# headers.net
KiCad netlist of a schematic drawn in Altium Designer
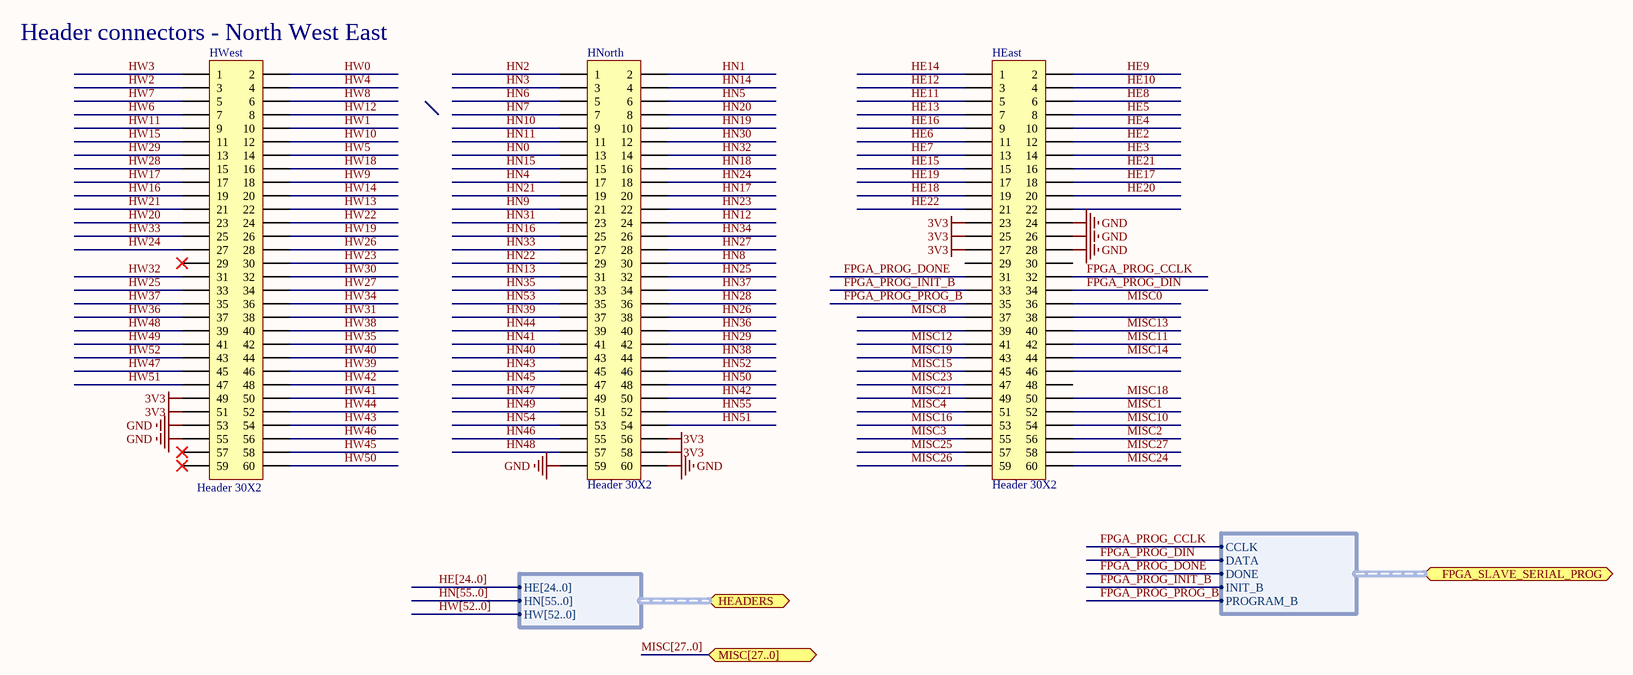
[diagram p0: headers.SchDoc]

(export (version "E")
  (design (tool "Eeschema 10.0.6"))
  (components
    (comp (ref "HEast")
      (value "Header 30X2")
      (footprint "HDR2X30")
      (description "Header, 30-Pin, Dual row")
      (fields (field (name "PUBLISHER") "Altium Limited"))
      (libsource (lib "Miscellaneous Connectors") (part "Header 30X2"))
    )
    (comp (ref "HNorth")
      (value "Header 30X2")
      (footprint "HDR2X30")
      (description "Header, 30-Pin, Dual row")
      (fields (field (name "PUBLISHER") "Altium Limited"))
      (libsource (lib "Miscellaneous Connectors") (part "Header 30X2"))
    )
    (comp (ref "HWest")
      (value "Header 30X2")
      (footprint "HDR2X30")
      (description "Header, 30-Pin, Dual row")
      (fields (field (name "PUBLISHER") "Altium Limited"))
      (libsource (lib "Miscellaneous Connectors") (part "Header 30X2"))
    )
  )
  (nets
    (net (code "10") (name "/FPGA_PROG_CCLK") (class "Default")
      (node (ref "HEast") (pin "32") (pinfunction "32_32") (pintype "passive"))
    )
    (net (code "11") (name "/FPGA_PROG_DIN") (class "Default")
      (node (ref "HEast") (pin "34") (pinfunction "34_34") (pintype "passive"))
    )
    (net (code "12") (name "/FPGA_PROG_DONE") (class "Default")
      (node (ref "HEast") (pin "31") (pinfunction "31_31") (pintype "passive"))
    )
    (net (code "13") (name "/FPGA_PROG_INIT_B") (class "Default")
      (node (ref "HEast") (pin "33") (pinfunction "33_33") (pintype "passive"))
    )
    (net (code "14") (name "/FPGA_PROG_PROG_B") (class "Default")
      (node (ref "HEast") (pin "35") (pinfunction "35_35") (pintype "passive"))
    )
    (net (code "15") (name "/HE2") (class "Default")
      (node (ref "HEast") (pin "12") (pinfunction "12_12") (pintype "passive"))
    )
    (net (code "16") (name "/HE3") (class "Default")
      (node (ref "HEast") (pin "14") (pinfunction "14_14") (pintype "passive"))
    )
    (net (code "17") (name "/HE4") (class "Default")
      (node (ref "HEast") (pin "10") (pinfunction "10_10") (pintype "passive"))
    )
    (net (code "18") (name "/HE5") (class "Default")
      (node (ref "HEast") (pin "8") (pinfunction "8_8") (pintype "passive"))
    )
    (net (code "19") (name "/HE6") (class "Default")
      (node (ref "HEast") (pin "11") (pinfunction "11_11") (pintype "passive"))
    )
    (net (code "20") (name "/HE7") (class "Default")
      (node (ref "HEast") (pin "13") (pinfunction "13_13") (pintype "passive"))
    )
    (net (code "21") (name "/HE8") (class "Default")
      (node (ref "HEast") (pin "6") (pinfunction "6_6") (pintype "passive"))
    )
    (net (code "22") (name "/HE9") (class "Default")
      (node (ref "HEast") (pin "2") (pinfunction "2_2") (pintype "passive"))
    )
    (net (code "23") (name "/HE10") (class "Default")
      (node (ref "HEast") (pin "4") (pinfunction "4_4") (pintype "passive"))
    )
    (net (code "24") (name "/HE11") (class "Default")
      (node (ref "HEast") (pin "5") (pinfunction "5_5") (pintype "passive"))
    )
    (net (code "25") (name "/HE12") (class "Default")
      (node (ref "HEast") (pin "3") (pinfunction "3_3") (pintype "passive"))
    )
    (net (code "26") (name "/HE13") (class "Default")
      (node (ref "HEast") (pin "7") (pinfunction "7_7") (pintype "passive"))
    )
    (net (code "27") (name "/HE14") (class "Default")
      (node (ref "HEast") (pin "1") (pinfunction "1_1") (pintype "passive"))
    )
    (net (code "28") (name "/HE15") (class "Default")
      (node (ref "HEast") (pin "15") (pinfunction "15_15") (pintype "passive"))
    )
    (net (code "29") (name "/HE16") (class "Default")
      (node (ref "HEast") (pin "9") (pinfunction "9_9") (pintype "passive"))
    )
    (net (code "30") (name "/HE17") (class "Default")
      (node (ref "HEast") (pin "18") (pinfunction "18_18") (pintype "passive"))
    )
    (net (code "31") (name "/HE18") (class "Default")
      (node (ref "HEast") (pin "19") (pinfunction "19_19") (pintype "passive"))
    )
    (net (code "32") (name "/HE19") (class "Default")
      (node (ref "HEast") (pin "17") (pinfunction "17_17") (pintype "passive"))
    )
    (net (code "33") (name "/HE20") (class "Default")
      (node (ref "HEast") (pin "20") (pinfunction "20_20") (pintype "passive"))
    )
    (net (code "34") (name "/HE21") (class "Default")
      (node (ref "HEast") (pin "16") (pinfunction "16_16") (pintype "passive"))
    )
    (net (code "35") (name "/HE22") (class "Default")
      (node (ref "HEast") (pin "21") (pinfunction "21_21") (pintype "passive"))
    )
    (net (code "37") (name "/HN0") (class "Default")
      (node (ref "HNorth") (pin "13") (pinfunction "13_13") (pintype "passive"))
    )
    (net (code "38") (name "/HN1") (class "Default")
      (node (ref "HNorth") (pin "2") (pinfunction "2_2") (pintype "passive"))
    )
    (net (code "39") (name "/HN2") (class "Default")
      (node (ref "HNorth") (pin "1") (pinfunction "1_1") (pintype "passive"))
    )
    (net (code "40") (name "/HN3") (class "Default")
      (node (ref "HNorth") (pin "3") (pinfunction "3_3") (pintype "passive"))
    )
    (net (code "41") (name "/HN4") (class "Default")
      (node (ref "HNorth") (pin "17") (pinfunction "17_17") (pintype "passive"))
    )
    (net (code "42") (name "/HN5") (class "Default")
      (node (ref "HNorth") (pin "6") (pinfunction "6_6") (pintype "passive"))
    )
    (net (code "43") (name "/HN6") (class "Default")
      (node (ref "HNorth") (pin "5") (pinfunction "5_5") (pintype "passive"))
    )
    (net (code "44") (name "/HN7") (class "Default")
      (node (ref "HNorth") (pin "7") (pinfunction "7_7") (pintype "passive"))
    )
    (net (code "45") (name "/HN8") (class "Default")
      (node (ref "HNorth") (pin "30") (pinfunction "30_30") (pintype "passive"))
    )
    (net (code "46") (name "/HN9") (class "Default")
      (node (ref "HNorth") (pin "21") (pinfunction "21_21") (pintype "passive"))
    )
    (net (code "47") (name "/HN10") (class "Default")
      (node (ref "HNorth") (pin "9") (pinfunction "9_9") (pintype "passive"))
    )
    (net (code "48") (name "/HN11") (class "Default")
      (node (ref "HNorth") (pin "11") (pinfunction "11_11") (pintype "passive"))
    )
    (net (code "49") (name "/HN12") (class "Default")
      (node (ref "HNorth") (pin "24") (pinfunction "24_24") (pintype "passive"))
    )
    (net (code "50") (name "/HN13") (class "Default")
      (node (ref "HNorth") (pin "31") (pinfunction "31_31") (pintype "passive"))
    )
    (net (code "51") (name "/HN14") (class "Default")
      (node (ref "HNorth") (pin "4") (pinfunction "4_4") (pintype "passive"))
    )
    (net (code "52") (name "/HN15") (class "Default")
      (node (ref "HNorth") (pin "15") (pinfunction "15_15") (pintype "passive"))
    )
    (net (code "53") (name "/HN16") (class "Default")
      (node (ref "HNorth") (pin "25") (pinfunction "25_25") (pintype "passive"))
    )
    (net (code "54") (name "/HN17") (class "Default")
      (node (ref "HNorth") (pin "20") (pinfunction "20_20") (pintype "passive"))
    )
    (net (code "55") (name "/HN18") (class "Default")
      (node (ref "HNorth") (pin "16") (pinfunction "16_16") (pintype "passive"))
    )
    (net (code "56") (name "/HN19") (class "Default")
      (node (ref "HNorth") (pin "10") (pinfunction "10_10") (pintype "passive"))
    )
    (net (code "57") (name "/HN20") (class "Default")
      (node (ref "HNorth") (pin "8") (pinfunction "8_8") (pintype "passive"))
    )
    (net (code "58") (name "/HN21") (class "Default")
      (node (ref "HNorth") (pin "19") (pinfunction "19_19") (pintype "passive"))
    )
    (net (code "59") (name "/HN22") (class "Default")
      (node (ref "HNorth") (pin "29") (pinfunction "29_29") (pintype "passive"))
    )
    (net (code "60") (name "/HN23") (class "Default")
      (node (ref "HNorth") (pin "22") (pinfunction "22_22") (pintype "passive"))
    )
    (net (code "61") (name "/HN24") (class "Default")
      (node (ref "HNorth") (pin "18") (pinfunction "18_18") (pintype "passive"))
    )
    (net (code "62") (name "/HN25") (class "Default")
      (node (ref "HNorth") (pin "32") (pinfunction "32_32") (pintype "passive"))
    )
    (net (code "63") (name "/HN26") (class "Default")
      (node (ref "HNorth") (pin "38") (pinfunction "38_38") (pintype "passive"))
    )
    (net (code "64") (name "/HN27") (class "Default")
      (node (ref "HNorth") (pin "28") (pinfunction "28_28") (pintype "passive"))
    )
    (net (code "65") (name "/HN28") (class "Default")
      (node (ref "HNorth") (pin "36") (pinfunction "36_36") (pintype "passive"))
    )
    (net (code "66") (name "/HN29") (class "Default")
      (node (ref "HNorth") (pin "42") (pinfunction "42_42") (pintype "passive"))
    )
    (net (code "67") (name "/HN30") (class "Default")
      (node (ref "HNorth") (pin "12") (pinfunction "12_12") (pintype "passive"))
    )
    (net (code "68") (name "/HN31") (class "Default")
      (node (ref "HNorth") (pin "23") (pinfunction "23_23") (pintype "passive"))
    )
    (net (code "69") (name "/HN32") (class "Default")
      (node (ref "HNorth") (pin "14") (pinfunction "14_14") (pintype "passive"))
    )
    (net (code "70") (name "/HN33") (class "Default")
      (node (ref "HNorth") (pin "27") (pinfunction "27_27") (pintype "passive"))
    )
    (net (code "71") (name "/HN34") (class "Default")
      (node (ref "HNorth") (pin "26") (pinfunction "26_26") (pintype "passive"))
    )
    (net (code "72") (name "/HN35") (class "Default")
      (node (ref "HNorth") (pin "33") (pinfunction "33_33") (pintype "passive"))
    )
    (net (code "73") (name "/HN36") (class "Default")
      (node (ref "HNorth") (pin "40") (pinfunction "40_40") (pintype "passive"))
    )
    (net (code "74") (name "/HN37") (class "Default")
      (node (ref "HNorth") (pin "34") (pinfunction "34_34") (pintype "passive"))
    )
    (net (code "75") (name "/HN38") (class "Default")
      (node (ref "HNorth") (pin "44") (pinfunction "44_44") (pintype "passive"))
    )
    (net (code "76") (name "/HN39") (class "Default")
      (node (ref "HNorth") (pin "37") (pinfunction "37_37") (pintype "passive"))
    )
    (net (code "77") (name "/HN40") (class "Default")
      (node (ref "HNorth") (pin "43") (pinfunction "43_43") (pintype "passive"))
    )
    (net (code "78") (name "/HN41") (class "Default")
      (node (ref "HNorth") (pin "41") (pinfunction "41_41") (pintype "passive"))
    )
    (net (code "79") (name "/HN42") (class "Default")
      (node (ref "HNorth") (pin "50") (pinfunction "50_50") (pintype "passive"))
    )
    (net (code "80") (name "/HN43") (class "Default")
      (node (ref "HNorth") (pin "45") (pinfunction "45_45") (pintype "passive"))
    )
    (net (code "81") (name "/HN44") (class "Default")
      (node (ref "HNorth") (pin "39") (pinfunction "39_39") (pintype "passive"))
    )
    (net (code "82") (name "/HN45") (class "Default")
      (node (ref "HNorth") (pin "47") (pinfunction "47_47") (pintype "passive"))
    )
    (net (code "83") (name "/HN46") (class "Default")
      (node (ref "HNorth") (pin "55") (pinfunction "55_55") (pintype "passive"))
    )
    (net (code "84") (name "/HN47") (class "Default")
      (node (ref "HNorth") (pin "49") (pinfunction "49_49") (pintype "passive"))
    )
    (net (code "85") (name "/HN48") (class "Default")
      (node (ref "HNorth") (pin "57") (pinfunction "57_57") (pintype "passive"))
    )
    (net (code "86") (name "/HN49") (class "Default")
      (node (ref "HNorth") (pin "51") (pinfunction "51_51") (pintype "passive"))
    )
    (net (code "87") (name "/HN50") (class "Default")
      (node (ref "HNorth") (pin "48") (pinfunction "48_48") (pintype "passive"))
    )
    (net (code "88") (name "/HN51") (class "Default")
      (node (ref "HNorth") (pin "54") (pinfunction "54_54") (pintype "passive"))
    )
    (net (code "89") (name "/HN52") (class "Default")
      (node (ref "HNorth") (pin "46") (pinfunction "46_46") (pintype "passive"))
    )
    (net (code "90") (name "/HN53") (class "Default")
      (node (ref "HNorth") (pin "35") (pinfunction "35_35") (pintype "passive"))
    )
    (net (code "91") (name "/HN54") (class "Default")
      (node (ref "HNorth") (pin "53") (pinfunction "53_53") (pintype "passive"))
    )
    (net (code "92") (name "/HN55") (class "Default")
      (node (ref "HNorth") (pin "52") (pinfunction "52_52") (pintype "passive"))
    )
    (net (code "94") (name "/HW0") (class "Default")
      (node (ref "HWest") (pin "2") (pinfunction "2_2") (pintype "passive"))
    )
    (net (code "95") (name "/HW1") (class "Default")
      (node (ref "HWest") (pin "10") (pinfunction "10_10") (pintype "passive"))
    )
    (net (code "96") (name "/HW2") (class "Default")
      (node (ref "HWest") (pin "3") (pinfunction "3_3") (pintype "passive"))
    )
    (net (code "97") (name "/HW3") (class "Default")
      (node (ref "HWest") (pin "1") (pinfunction "1_1") (pintype "passive"))
    )
    (net (code "98") (name "/HW4") (class "Default")
      (node (ref "HWest") (pin "4") (pinfunction "4_4") (pintype "passive"))
    )
    (net (code "99") (name "/HW5") (class "Default")
      (node (ref "HWest") (pin "14") (pinfunction "14_14") (pintype "passive"))
    )
    (net (code "100") (name "/HW6") (class "Default")
      (node (ref "HWest") (pin "7") (pinfunction "7_7") (pintype "passive"))
    )
    (net (code "101") (name "/HW7") (class "Default")
      (node (ref "HWest") (pin "5") (pinfunction "5_5") (pintype "passive"))
    )
    (net (code "102") (name "/HW8") (class "Default")
      (node (ref "HWest") (pin "6") (pinfunction "6_6") (pintype "passive"))
    )
    (net (code "103") (name "/HW9") (class "Default")
      (node (ref "HWest") (pin "18") (pinfunction "18_18") (pintype "passive"))
    )
    (net (code "104") (name "/HW10") (class "Default")
      (node (ref "HWest") (pin "12") (pinfunction "12_12") (pintype "passive"))
    )
    (net (code "105") (name "/HW11") (class "Default")
      (node (ref "HWest") (pin "9") (pinfunction "9_9") (pintype "passive"))
    )
    (net (code "106") (name "/HW12") (class "Default")
      (node (ref "HWest") (pin "8") (pinfunction "8_8") (pintype "passive"))
    )
    (net (code "107") (name "/HW13") (class "Default")
      (node (ref "HWest") (pin "22") (pinfunction "22_22") (pintype "passive"))
    )
    (net (code "108") (name "/HW14") (class "Default")
      (node (ref "HWest") (pin "20") (pinfunction "20_20") (pintype "passive"))
    )
    (net (code "109") (name "/HW15") (class "Default")
      (node (ref "HWest") (pin "11") (pinfunction "11_11") (pintype "passive"))
    )
    (net (code "110") (name "/HW16") (class "Default")
      (node (ref "HWest") (pin "19") (pinfunction "19_19") (pintype "passive"))
    )
    (net (code "111") (name "/HW17") (class "Default")
      (node (ref "HWest") (pin "17") (pinfunction "17_17") (pintype "passive"))
    )
    (net (code "112") (name "/HW18") (class "Default")
      (node (ref "HWest") (pin "16") (pinfunction "16_16") (pintype "passive"))
    )
    (net (code "113") (name "/HW19") (class "Default")
      (node (ref "HWest") (pin "26") (pinfunction "26_26") (pintype "passive"))
    )
    (net (code "114") (name "/HW20") (class "Default")
      (node (ref "HWest") (pin "23") (pinfunction "23_23") (pintype "passive"))
    )
    (net (code "115") (name "/HW21") (class "Default")
      (node (ref "HWest") (pin "21") (pinfunction "21_21") (pintype "passive"))
    )
    (net (code "116") (name "/HW22") (class "Default")
      (node (ref "HWest") (pin "24") (pinfunction "24_24") (pintype "passive"))
    )
    (net (code "117") (name "/HW23") (class "Default")
      (node (ref "HWest") (pin "30") (pinfunction "30_30") (pintype "passive"))
    )
    (net (code "118") (name "/HW24") (class "Default")
      (node (ref "HWest") (pin "27") (pinfunction "27_27") (pintype "passive"))
    )
    (net (code "119") (name "/HW25") (class "Default")
      (node (ref "HWest") (pin "33") (pinfunction "33_33") (pintype "passive"))
    )
    (net (code "120") (name "/HW26") (class "Default")
      (node (ref "HWest") (pin "28") (pinfunction "28_28") (pintype "passive"))
    )
    (net (code "121") (name "/HW27") (class "Default")
      (node (ref "HWest") (pin "34") (pinfunction "34_34") (pintype "passive"))
    )
    (net (code "122") (name "/HW28") (class "Default")
      (node (ref "HWest") (pin "15") (pinfunction "15_15") (pintype "passive"))
    )
    (net (code "123") (name "/HW29") (class "Default")
      (node (ref "HWest") (pin "13") (pinfunction "13_13") (pintype "passive"))
    )
    (net (code "124") (name "/HW30") (class "Default")
      (node (ref "HWest") (pin "32") (pinfunction "32_32") (pintype "passive"))
    )
    (net (code "125") (name "/HW31") (class "Default")
      (node (ref "HWest") (pin "38") (pinfunction "38_38") (pintype "passive"))
    )
    (net (code "126") (name "/HW32") (class "Default")
      (node (ref "HWest") (pin "31") (pinfunction "31_31") (pintype "passive"))
    )
    (net (code "127") (name "/HW33") (class "Default")
      (node (ref "HWest") (pin "25") (pinfunction "25_25") (pintype "passive"))
    )
    (net (code "128") (name "/HW34") (class "Default")
      (node (ref "HWest") (pin "36") (pinfunction "36_36") (pintype "passive"))
    )
    (net (code "129") (name "/HW35") (class "Default")
      (node (ref "HWest") (pin "42") (pinfunction "42_42") (pintype "passive"))
    )
    (net (code "130") (name "/HW36") (class "Default")
      (node (ref "HWest") (pin "37") (pinfunction "37_37") (pintype "passive"))
    )
    (net (code "131") (name "/HW37") (class "Default")
      (node (ref "HWest") (pin "35") (pinfunction "35_35") (pintype "passive"))
    )
    (net (code "132") (name "/HW38") (class "Default")
      (node (ref "HWest") (pin "40") (pinfunction "40_40") (pintype "passive"))
    )
    (net (code "133") (name "/HW39") (class "Default")
      (node (ref "HWest") (pin "46") (pinfunction "46_46") (pintype "passive"))
    )
    (net (code "134") (name "/HW40") (class "Default")
      (node (ref "HWest") (pin "44") (pinfunction "44_44") (pintype "passive"))
    )
    (net (code "135") (name "/HW41") (class "Default")
      (node (ref "HWest") (pin "50") (pinfunction "50_50") (pintype "passive"))
    )
    (net (code "136") (name "/HW42") (class "Default")
      (node (ref "HWest") (pin "48") (pinfunction "48_48") (pintype "passive"))
    )
    (net (code "137") (name "/HW43") (class "Default")
      (node (ref "HWest") (pin "54") (pinfunction "54_54") (pintype "passive"))
    )
    (net (code "138") (name "/HW44") (class "Default")
      (node (ref "HWest") (pin "52") (pinfunction "52_52") (pintype "passive"))
    )
    (net (code "139") (name "/HW45") (class "Default")
      (node (ref "HWest") (pin "58") (pinfunction "58_58") (pintype "passive"))
    )
    (net (code "140") (name "/HW46") (class "Default")
      (node (ref "HWest") (pin "56") (pinfunction "56_56") (pintype "passive"))
    )
    (net (code "141") (name "/HW47") (class "Default")
      (node (ref "HWest") (pin "45") (pinfunction "45_45") (pintype "passive"))
    )
    (net (code "142") (name "/HW48") (class "Default")
      (node (ref "HWest") (pin "39") (pinfunction "39_39") (pintype "passive"))
    )
    (net (code "143") (name "/HW49") (class "Default")
      (node (ref "HWest") (pin "41") (pinfunction "41_41") (pintype "passive"))
    )
    (net (code "144") (name "/HW50") (class "Default")
      (node (ref "HWest") (pin "60") (pinfunction "60_60") (pintype "passive"))
    )
    (net (code "145") (name "/HW51") (class "Default")
      (node (ref "HWest") (pin "47") (pinfunction "47_47") (pintype "passive"))
    )
    (net (code "146") (name "/HW52") (class "Default")
      (node (ref "HWest") (pin "43") (pinfunction "43_43") (pintype "passive"))
    )
    (net (code "148") (name "/MISC0") (class "Default")
      (node (ref "HEast") (pin "36") (pinfunction "36_36") (pintype "passive"))
    )
    (net (code "149") (name "/MISC1") (class "Default")
      (node (ref "HEast") (pin "52") (pinfunction "52_52") (pintype "passive"))
    )
    (net (code "150") (name "/MISC2") (class "Default")
      (node (ref "HEast") (pin "56") (pinfunction "56_56") (pintype "passive"))
    )
    (net (code "151") (name "/MISC3") (class "Default")
      (node (ref "HEast") (pin "55") (pinfunction "55_55") (pintype "passive"))
    )
    (net (code "152") (name "/MISC4") (class "Default")
      (node (ref "HEast") (pin "51") (pinfunction "51_51") (pintype "passive"))
    )
    (net (code "153") (name "/MISC8") (class "Default")
      (node (ref "HEast") (pin "37") (pinfunction "37_37") (pintype "passive"))
    )
    (net (code "154") (name "/MISC10") (class "Default")
      (node (ref "HEast") (pin "54") (pinfunction "54_54") (pintype "passive"))
    )
    (net (code "155") (name "/MISC11") (class "Default")
      (node (ref "HEast") (pin "42") (pinfunction "42_42") (pintype "passive"))
    )
    (net (code "156") (name "/MISC12") (class "Default")
      (node (ref "HEast") (pin "41") (pinfunction "41_41") (pintype "passive"))
    )
    (net (code "157") (name "/MISC13") (class "Default")
      (node (ref "HEast") (pin "40") (pinfunction "40_40") (pintype "passive"))
    )
    (net (code "158") (name "/MISC14") (class "Default")
      (node (ref "HEast") (pin "44") (pinfunction "44_44") (pintype "passive"))
    )
    (net (code "159") (name "/MISC15") (class "Default")
      (node (ref "HEast") (pin "45") (pinfunction "45_45") (pintype "passive"))
    )
    (net (code "160") (name "/MISC16") (class "Default")
      (node (ref "HEast") (pin "53") (pinfunction "53_53") (pintype "passive"))
    )
    (net (code "161") (name "/MISC18") (class "Default")
      (node (ref "HEast") (pin "50") (pinfunction "50_50") (pintype "passive"))
    )
    (net (code "162") (name "/MISC19") (class "Default")
      (node (ref "HEast") (pin "43") (pinfunction "43_43") (pintype "passive"))
    )
    (net (code "163") (name "/MISC21") (class "Default")
      (node (ref "HEast") (pin "49") (pinfunction "49_49") (pintype "passive"))
    )
    (net (code "164") (name "/MISC23") (class "Default")
      (node (ref "HEast") (pin "47") (pinfunction "47_47") (pintype "passive"))
    )
    (net (code "165") (name "/MISC24") (class "Default")
      (node (ref "HEast") (pin "60") (pinfunction "60_60") (pintype "passive"))
    )
    (net (code "166") (name "/MISC25") (class "Default")
      (node (ref "HEast") (pin "57") (pinfunction "57_57") (pintype "passive"))
    )
    (net (code "167") (name "/MISC26") (class "Default")
      (node (ref "HEast") (pin "59") (pinfunction "59_59") (pintype "passive"))
    )
    (net (code "168") (name "/MISC27") (class "Default")
      (node (ref "HEast") (pin "58") (pinfunction "58_58") (pintype "passive"))
    )
    (net (code "171") (name "3V3") (class "Default")
      (node (ref "HEast") (pin "23") (pinfunction "23_23") (pintype "passive"))
      (node (ref "HEast") (pin "25") (pinfunction "25_25") (pintype "passive"))
      (node (ref "HEast") (pin "27") (pinfunction "27_27") (pintype "passive"))
      (node (ref "HNorth") (pin "56") (pinfunction "56_56") (pintype "passive"))
      (node (ref "HNorth") (pin "58") (pinfunction "58_58") (pintype "passive"))
      (node (ref "HWest") (pin "49") (pinfunction "49_49") (pintype "passive"))
      (node (ref "HWest") (pin "51") (pinfunction "51_51") (pintype "passive"))
    )
    (net (code "172") (name "GND") (class "Default")
      (node (ref "HEast") (pin "24") (pinfunction "24_24") (pintype "passive"))
      (node (ref "HEast") (pin "26") (pinfunction "26_26") (pintype "passive"))
      (node (ref "HEast") (pin "28") (pinfunction "28_28") (pintype "passive"))
      (node (ref "HNorth") (pin "59") (pinfunction "59_59") (pintype "passive"))
      (node (ref "HNorth") (pin "60") (pinfunction "60_60") (pintype "passive"))
      (node (ref "HWest") (pin "53") (pinfunction "53_53") (pintype "passive"))
      (node (ref "HWest") (pin "55") (pinfunction "55_55") (pintype "passive"))
    )
    (net (code "173") (name "unconnected-(HEast-Pad22)") (class "Default")
      (node (ref "HEast") (pin "22") (pinfunction "22_22") (pintype "passive"))
    )
    (net (code "174") (name "unconnected-(HEast-Pad29)") (class "Default")
      (node (ref "HEast") (pin "29") (pinfunction "29_29") (pintype "passive"))
    )
    (net (code "175") (name "unconnected-(HEast-Pad30)") (class "Default")
      (node (ref "HEast") (pin "30") (pinfunction "30_30") (pintype "passive"))
    )
    (net (code "176") (name "unconnected-(HEast-Pad38)") (class "Default")
      (node (ref "HEast") (pin "38") (pinfunction "38_38") (pintype "passive"))
    )
    (net (code "177") (name "unconnected-(HEast-Pad39)") (class "Default")
      (node (ref "HEast") (pin "39") (pinfunction "39_39") (pintype "passive"))
    )
    (net (code "178") (name "unconnected-(HEast-Pad46)") (class "Default")
      (node (ref "HEast") (pin "46") (pinfunction "46_46") (pintype "passive"))
    )
    (net (code "179") (name "unconnected-(HEast-Pad48)") (class "Default")
      (node (ref "HEast") (pin "48") (pinfunction "48_48") (pintype "passive"))
    )
    (net (code "180") (name "unconnected-(HWest-Pad29)") (class "Default")
      (node (ref "HWest") (pin "29") (pinfunction "29_29") (pintype "passive+no_connect"))
    )
    (net (code "181") (name "unconnected-(HWest-Pad57)") (class "Default")
      (node (ref "HWest") (pin "57") (pinfunction "57_57") (pintype "passive+no_connect"))
    )
    (net (code "182") (name "unconnected-(HWest-Pad59)") (class "Default")
      (node (ref "HWest") (pin "59") (pinfunction "59_59") (pintype "passive+no_connect"))
    )
  )
)
